# washing-machine.net
KiCad netlist of a schematic drawn in EAGLE
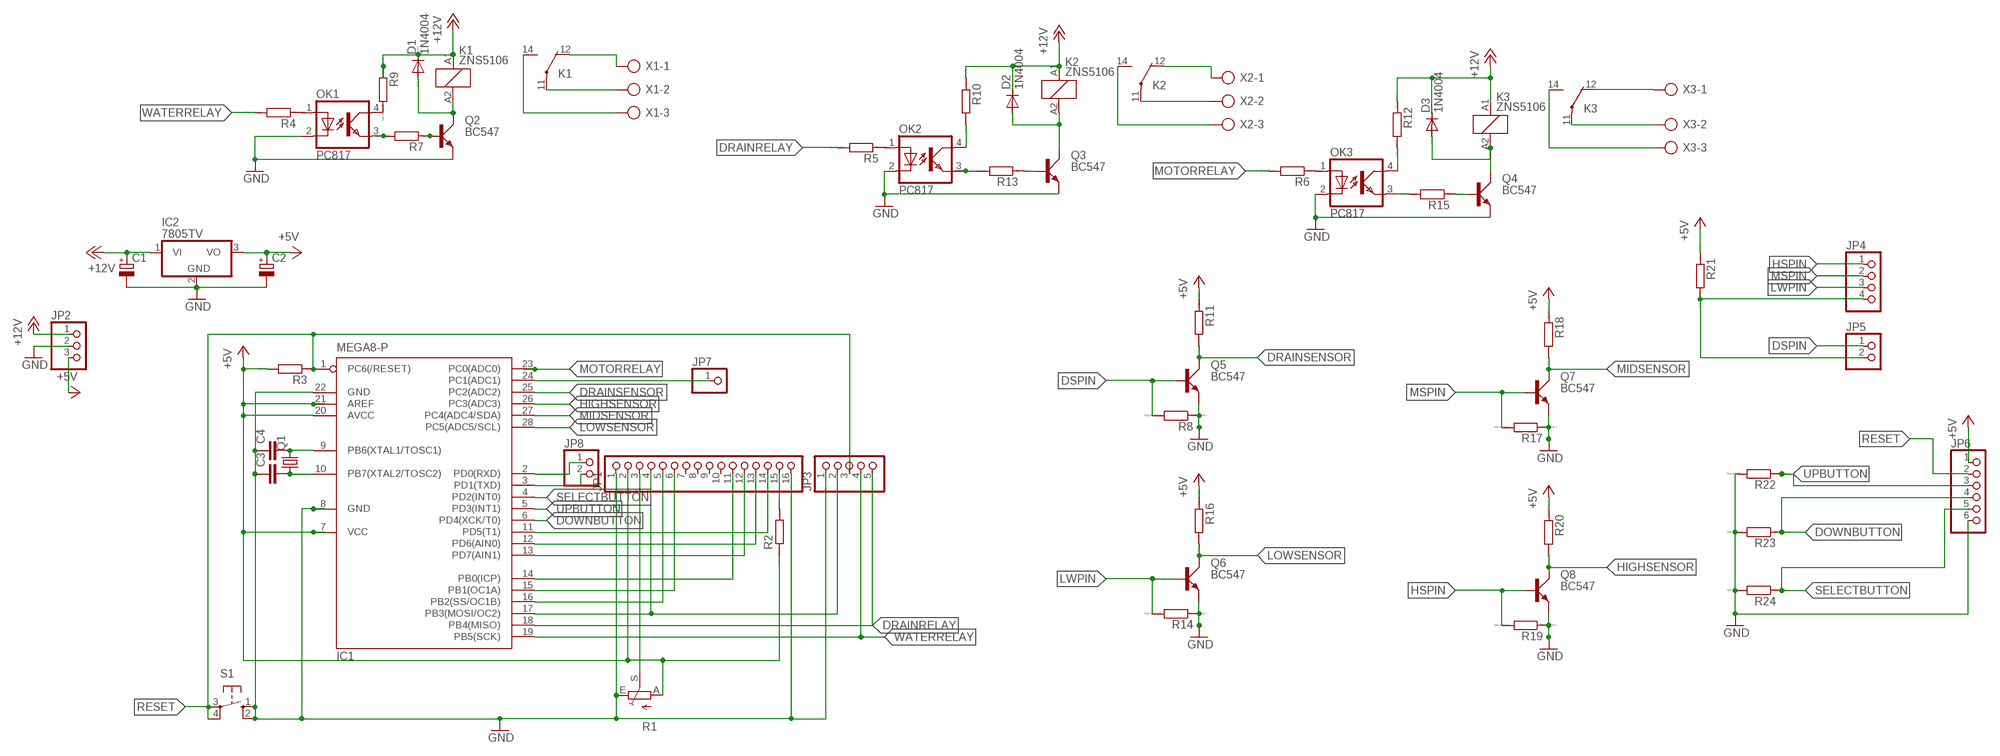
[diagram p0: schematic, sheet 1]

(export (version "E")
  (design (tool "Eeschema 10.0.6"))
  (components
    (comp (ref "C1")
      (value "CPOL-EUE1.8-4")
      (footprint "eagle-import:E1,8-4")
      (libsource (lib "eagle-import") (part "CPOL-EUE1.8-4"))
    )
    (comp (ref "C2")
      (value "CPOL-EUE1.8-4")
      (footprint "eagle-import:E1,8-4")
      (libsource (lib "eagle-import") (part "CPOL-EUE1.8-4"))
    )
    (comp (ref "C3")
      (value "C-EU025-024X044")
      (footprint "eagle-import:C025-024X044")
      (libsource (lib "eagle-import") (part "C-EU025-024X044"))
    )
    (comp (ref "C4")
      (value "C-EU025-024X044")
      (footprint "eagle-import:C025-024X044")
      (libsource (lib "eagle-import") (part "C-EU025-024X044"))
    )
    (comp (ref "D1")
      (value "1N4004")
      (footprint "eagle-import:DO41-10")
      (libsource (lib "eagle-import") (part "1N4004"))
    )
    (comp (ref "D2")
      (value "1N4004")
      (footprint "eagle-import:DO41-10")
      (libsource (lib "eagle-import") (part "1N4004"))
    )
    (comp (ref "D3")
      (value "1N4004")
      (footprint "eagle-import:DO41-10")
      (libsource (lib "eagle-import") (part "1N4004"))
    )
    (comp (ref "IC1")
      (value "MEGA8-P")
      (footprint "eagle-import:DIL28-3")
      (libsource (lib "eagle-import") (part "MEGA8-P"))
    )
    (comp (ref "IC2")
      (value "7805TV")
      (footprint "eagle-import:TO220V")
      (libsource (lib "eagle-import") (part "78TV05"))
    )
    (comp (ref "JP1")
      (value "PINHD-1X16")
      (footprint "eagle-import:1X16")
      (libsource (lib "eagle-import") (part "PINHD-1X16"))
    )
    (comp (ref "JP2")
      (value "PINHD-1X3")
      (footprint "eagle-import:1X03")
      (libsource (lib "eagle-import") (part "PINHD-1X3"))
    )
    (comp (ref "JP3")
      (value "PINHD-1X5")
      (footprint "eagle-import:1X05")
      (libsource (lib "eagle-import") (part "PINHD-1X5"))
    )
    (comp (ref "JP4")
      (value "PINHD-1X4")
      (footprint "eagle-import:1X04")
      (libsource (lib "eagle-import") (part "PINHD-1X4"))
    )
    (comp (ref "JP5")
      (value "PINHD-1X2")
      (footprint "eagle-import:1X02")
      (libsource (lib "eagle-import") (part "PINHD-1X2"))
    )
    (comp (ref "JP6")
      (value "PINHD-1X6")
      (footprint "eagle-import:1X06")
      (libsource (lib "eagle-import") (part "PINHD-1X6"))
    )
    (comp (ref "JP7")
      (value "PINHD-1X1")
      (footprint "eagle-import:1X01")
      (libsource (lib "eagle-import") (part "PINHD-1X1"))
    )
    (comp (ref "JP8")
      (value "PINHD-1X2")
      (footprint "eagle-import:1X02")
      (libsource (lib "eagle-import") (part "PINHD-1X2"))
    )
    (comp (ref "K1")
      (value "ZNS5106")
      (footprint "eagle-import:ZN5")
      (libsource (lib "eagle-import") (part "ZNS5106"))
    )
    (comp (ref "K2")
      (value "ZNS5106")
      (footprint "eagle-import:ZN5")
      (libsource (lib "eagle-import") (part "ZNS5106"))
    )
    (comp (ref "K3")
      (value "ZNS5106")
      (footprint "eagle-import:ZN5")
      (libsource (lib "eagle-import") (part "ZNS5106"))
    )
    (comp (ref "OK1")
      (value "PC817")
      (footprint "eagle-import:DIL04")
      (fields (field (name "MPN") "PC817X4J000F"))
      (libsource (lib "eagle-import") (part "PC817"))
    )
    (comp (ref "OK2")
      (value "PC817")
      (footprint "eagle-import:DIL04")
      (fields (field (name "MPN") "PC817X4J000F"))
      (libsource (lib "eagle-import") (part "PC817"))
    )
    (comp (ref "OK3")
      (value "PC817")
      (footprint "eagle-import:DIL04")
      (fields (field (name "MPN") "PC817X4J000F"))
      (libsource (lib "eagle-import") (part "PC817"))
    )
    (comp (ref "Q1")
      (value "CRYSTALHC49S")
      (footprint "eagle-import:HC49_S")
      (libsource (lib "eagle-import") (part "CRYSTALHC49S"))
    )
    (comp (ref "Q2")
      (value "BC547")
      (footprint "eagle-import:SOT54A")
      (libsource (lib "eagle-import") (part "BC547"))
    )
    (comp (ref "Q3")
      (value "BC547")
      (footprint "eagle-import:SOT54A")
      (libsource (lib "eagle-import") (part "BC547"))
    )
    (comp (ref "Q4")
      (value "BC547")
      (footprint "eagle-import:SOT54A")
      (libsource (lib "eagle-import") (part "BC547"))
    )
    (comp (ref "Q5")
      (value "BC547")
      (footprint "eagle-import:SOT54A")
      (libsource (lib "eagle-import") (part "BC547"))
    )
    (comp (ref "Q6")
      (value "BC547")
      (footprint "eagle-import:SOT54A")
      (libsource (lib "eagle-import") (part "BC547"))
    )
    (comp (ref "Q7")
      (value "BC547")
      (footprint "eagle-import:SOT54A")
      (libsource (lib "eagle-import") (part "BC547"))
    )
    (comp (ref "Q8")
      (value "BC547")
      (footprint "eagle-import:SOT54A")
      (libsource (lib "eagle-import") (part "BC547"))
    )
    (comp (ref "R1")
      (value "TRIM_EU-S63P")
      (footprint "eagle-import:S63P")
      (libsource (lib "eagle-import") (part "TRIM_EU-S63P"))
    )
    (comp (ref "R2")
      (value "R0204/7")
      (footprint "eagle-import:0204_7")
      (libsource (lib "eagle-import") (part "R0204/7"))
    )
    (comp (ref "R3")
      (value "R0204/7")
      (footprint "eagle-import:0204_7")
      (libsource (lib "eagle-import") (part "R0204/7"))
    )
    (comp (ref "R4")
      (value "R0204/7")
      (footprint "eagle-import:0204_7")
      (libsource (lib "eagle-import") (part "R0204/7"))
    )
    (comp (ref "R5")
      (value "R0204/7")
      (footprint "eagle-import:0204_7")
      (libsource (lib "eagle-import") (part "R0204/7"))
    )
    (comp (ref "R6")
      (value "R0204/7")
      (footprint "eagle-import:0204_7")
      (libsource (lib "eagle-import") (part "R0204/7"))
    )
    (comp (ref "R7")
      (value "R0204/7")
      (footprint "eagle-import:0204_7")
      (libsource (lib "eagle-import") (part "R0204/7"))
    )
    (comp (ref "R8")
      (value "R0204/7")
      (footprint "eagle-import:0204_7")
      (libsource (lib "eagle-import") (part "R0204/7"))
    )
    (comp (ref "R9")
      (value "R0204/7")
      (footprint "eagle-import:0204_7")
      (libsource (lib "eagle-import") (part "R0204/7"))
    )
    (comp (ref "R10")
      (value "R0204/7")
      (footprint "eagle-import:0204_7")
      (libsource (lib "eagle-import") (part "R0204/7"))
    )
    (comp (ref "R11")
      (value "R0204/7")
      (footprint "eagle-import:0204_7")
      (libsource (lib "eagle-import") (part "R0204/7"))
    )
    (comp (ref "R12")
      (value "R0204/7")
      (footprint "eagle-import:0204_7")
      (libsource (lib "eagle-import") (part "R0204/7"))
    )
    (comp (ref "R13")
      (value "R0204/7")
      (footprint "eagle-import:0204_7")
      (libsource (lib "eagle-import") (part "R0204/7"))
    )
    (comp (ref "R14")
      (value "R0204/7")
      (footprint "eagle-import:0204_7")
      (libsource (lib "eagle-import") (part "R0204/7"))
    )
    (comp (ref "R15")
      (value "R0204/7")
      (footprint "eagle-import:0204_7")
      (libsource (lib "eagle-import") (part "R0204/7"))
    )
    (comp (ref "R16")
      (value "R0204/7")
      (footprint "eagle-import:0204_7")
      (libsource (lib "eagle-import") (part "R0204/7"))
    )
    (comp (ref "R17")
      (value "R0204/7")
      (footprint "eagle-import:0204_7")
      (libsource (lib "eagle-import") (part "R0204/7"))
    )
    (comp (ref "R18")
      (value "R0204/7")
      (footprint "eagle-import:0204_7")
      (libsource (lib "eagle-import") (part "R0204/7"))
    )
    (comp (ref "R19")
      (value "R0204/7")
      (footprint "eagle-import:0204_7")
      (libsource (lib "eagle-import") (part "R0204/7"))
    )
    (comp (ref "R20")
      (value "R0204/7")
      (footprint "eagle-import:0204_7")
      (libsource (lib "eagle-import") (part "R0204/7"))
    )
    (comp (ref "R21")
      (value "R0204/7")
      (footprint "eagle-import:0204_7")
      (libsource (lib "eagle-import") (part "R0204/7"))
    )
    (comp (ref "R22")
      (value "R0204/7")
      (footprint "eagle-import:0204_7")
      (libsource (lib "eagle-import") (part "R0204/7"))
    )
    (comp (ref "R23")
      (value "R0204/7")
      (footprint "eagle-import:0204_7")
      (libsource (lib "eagle-import") (part "R0204/7"))
    )
    (comp (ref "R24")
      (value "R0204/7")
      (footprint "eagle-import:0204_7")
      (libsource (lib "eagle-import") (part "R0204/7"))
    )
    (comp (ref "S1")
      (value "10-XX")
      (footprint "eagle-import:B3F-10XX")
      (fields (field (name "MPN") "B3F-1000"))
      (libsource (lib "eagle-import") (part "10-XX"))
    )
    (comp (ref "X1")
      (value "AK500/3")
      (footprint "eagle-import:AK500_3")
      (libsource (lib "eagle-import") (part "AK500/3"))
    )
    (comp (ref "X2")
      (value "AK500/3")
      (footprint "eagle-import:AK500_3")
      (libsource (lib "eagle-import") (part "AK500/3"))
    )
    (comp (ref "X3")
      (value "AK500/3")
      (footprint "eagle-import:AK500_3")
      (libsource (lib "eagle-import") (part "AK500/3"))
    )
  )
  (nets
    (net (code "1") (name "+5V") (class "Default")
      (node (ref "C2") (pin "+") (pinfunction "+_+") (pintype "passive"))
      (node (ref "IC1") (pin "20") (pinfunction "AVCC_20") (pintype "power_in"))
      (node (ref "IC1") (pin "21") (pinfunction "AREF_21") (pintype "passive"))
      (node (ref "IC1") (pin "7") (pinfunction "VCC_7") (pintype "power_in"))
      (node (ref "IC2") (pin "3") (pinfunction "VO_3") (pintype "passive"))
      (node (ref "JP1") (pin "2") (pinfunction "2_2") (pintype "passive"))
      (node (ref "JP2") (pin "3") (pinfunction "3_3") (pintype "passive"))
      (node (ref "JP6") (pin "1") (pinfunction "1_1") (pintype "passive"))
      (node (ref "R1") (pin "A") (pinfunction "A_A") (pintype "passive"))
      (node (ref "R11") (pin "1") (pinfunction "1_1") (pintype "passive"))
      (node (ref "R16") (pin "1") (pinfunction "1_1") (pintype "passive"))
      (node (ref "R18") (pin "1") (pinfunction "1_1") (pintype "passive"))
      (node (ref "R2") (pin "1") (pinfunction "1_1") (pintype "passive"))
      (node (ref "R20") (pin "1") (pinfunction "1_1") (pintype "passive"))
      (node (ref "R21") (pin "1") (pinfunction "1_1") (pintype "passive"))
      (node (ref "R3") (pin "2") (pinfunction "2_2") (pintype "passive"))
    )
    (net (code "2") (name "+12V") (class "Default")
      (node (ref "C1") (pin "+") (pinfunction "+_+") (pintype "passive"))
      (node (ref "D1") (pin "C") (pinfunction "C_C") (pintype "passive"))
      (node (ref "D2") (pin "C") (pinfunction "C_C") (pintype "passive"))
      (node (ref "D3") (pin "C") (pinfunction "C_C") (pintype "passive"))
      (node (ref "IC2") (pin "1") (pinfunction "VI_1") (pintype "input"))
      (node (ref "JP2") (pin "1") (pinfunction "1_1") (pintype "passive"))
      (node (ref "K1") (pin "A1") (pinfunction "1_A1") (pintype "passive"))
      (node (ref "K2") (pin "A1") (pinfunction "1_A1") (pintype "passive"))
      (node (ref "K3") (pin "A1") (pinfunction "1_A1") (pintype "passive"))
      (node (ref "R10") (pin "1") (pinfunction "1_1") (pintype "passive"))
      (node (ref "R12") (pin "1") (pinfunction "1_1") (pintype "passive"))
      (node (ref "R9") (pin "1") (pinfunction "1_1") (pintype "passive"))
    )
    (net (code "3") (name "DOWNBUTTON") (class "Default")
      (node (ref "IC1") (pin "6") (pinfunction "PD4(XCK/T0)_6") (pintype "bidirectional"))
      (node (ref "JP6") (pin "4") (pinfunction "4_4") (pintype "passive"))
      (node (ref "R23") (pin "1") (pinfunction "1_1") (pintype "passive"))
    )
    (net (code "4") (name "DRAINRELAY") (class "Default")
      (node (ref "IC1") (pin "18") (pinfunction "PB4(MISO)_18") (pintype "bidirectional"))
      (node (ref "JP3") (pin "5") (pinfunction "5_5") (pintype "passive"))
      (node (ref "R5") (pin "2") (pinfunction "2_2") (pintype "passive"))
    )
    (net (code "5") (name "DRAINSENSOR") (class "Default")
      (node (ref "IC1") (pin "25") (pinfunction "PC2(ADC2)_25") (pintype "bidirectional"))
      (node (ref "Q5") (pin "C") (pinfunction "C_C") (pintype "passive"))
      (node (ref "R11") (pin "2") (pinfunction "2_2") (pintype "passive"))
    )
    (net (code "6") (name "DSPIN") (class "Default")
      (node (ref "JP5") (pin "1") (pinfunction "1_1") (pintype "passive"))
      (node (ref "Q5") (pin "B") (pinfunction "B_B") (pintype "passive"))
      (node (ref "R8") (pin "2") (pinfunction "2_2") (pintype "passive"))
    )
    (net (code "7") (name "GND") (class "Default")
      (node (ref "C1") (pin "-") (pinfunction "-_-") (pintype "passive"))
      (node (ref "C2") (pin "-") (pinfunction "-_-") (pintype "passive"))
      (node (ref "C3") (pin "1") (pinfunction "1_1") (pintype "passive"))
      (node (ref "C4") (pin "1") (pinfunction "1_1") (pintype "passive"))
      (node (ref "IC1") (pin "22") (pinfunction "GND_22") (pintype "power_in"))
      (node (ref "IC1") (pin "8") (pinfunction "GND_8") (pintype "power_in"))
      (node (ref "IC2") (pin "2") (pinfunction "GND_2") (pintype "passive"))
      (node (ref "JP1") (pin "1") (pinfunction "1_1") (pintype "passive"))
      (node (ref "JP1") (pin "16") (pinfunction "16_16") (pintype "passive"))
      (node (ref "JP2") (pin "2") (pinfunction "2_2") (pintype "passive"))
      (node (ref "JP3") (pin "1") (pinfunction "1_1") (pintype "passive"))
      (node (ref "JP6") (pin "6") (pinfunction "6_6") (pintype "passive"))
      (node (ref "OK1") (pin "2") (pinfunction "C_2") (pintype "passive"))
      (node (ref "OK2") (pin "2") (pinfunction "C_2") (pintype "passive"))
      (node (ref "OK3") (pin "2") (pinfunction "C_2") (pintype "passive"))
      (node (ref "Q2") (pin "E") (pinfunction "E_E") (pintype "passive"))
      (node (ref "Q3") (pin "E") (pinfunction "E_E") (pintype "passive"))
      (node (ref "Q4") (pin "E") (pinfunction "E_E") (pintype "passive"))
      (node (ref "Q5") (pin "E") (pinfunction "E_E") (pintype "passive"))
      (node (ref "Q6") (pin "E") (pinfunction "E_E") (pintype "passive"))
      (node (ref "Q7") (pin "E") (pinfunction "E_E") (pintype "passive"))
      (node (ref "Q8") (pin "E") (pinfunction "E_E") (pintype "passive"))
      (node (ref "R1") (pin "E") (pinfunction "E_E") (pintype "passive"))
      (node (ref "R14") (pin "1") (pinfunction "1_1") (pintype "passive"))
      (node (ref "R17") (pin "1") (pinfunction "1_1") (pintype "passive"))
      (node (ref "R19") (pin "1") (pinfunction "1_1") (pintype "passive"))
      (node (ref "R22") (pin "2") (pinfunction "2_2") (pintype "passive"))
      (node (ref "R23") (pin "2") (pinfunction "2_2") (pintype "passive"))
      (node (ref "R24") (pin "2") (pinfunction "2_2") (pintype "passive"))
      (node (ref "R8") (pin "1") (pinfunction "1_1") (pintype "passive"))
      (node (ref "S1") (pin "1") (pinfunction "S_1") (pintype "passive"))
      (node (ref "S1") (pin "2") (pinfunction "S1_2") (pintype "passive"))
    )
    (net (code "8") (name "HIGHSENSOR") (class "Default")
      (node (ref "IC1") (pin "26") (pinfunction "PC3(ADC3)_26") (pintype "bidirectional"))
      (node (ref "Q8") (pin "C") (pinfunction "C_C") (pintype "passive"))
      (node (ref "R20") (pin "2") (pinfunction "2_2") (pintype "passive"))
    )
    (net (code "9") (name "HSPIN") (class "Default")
      (node (ref "JP4") (pin "1") (pinfunction "1_1") (pintype "passive"))
      (node (ref "Q8") (pin "B") (pinfunction "B_B") (pintype "passive"))
      (node (ref "R19") (pin "2") (pinfunction "2_2") (pintype "passive"))
    )
    (net (code "10") (name "LOWSENSOR") (class "Default")
      (node (ref "IC1") (pin "28") (pinfunction "PC5(ADC5/SCL)_28") (pintype "bidirectional"))
      (node (ref "Q6") (pin "C") (pinfunction "C_C") (pintype "passive"))
      (node (ref "R16") (pin "2") (pinfunction "2_2") (pintype "passive"))
    )
    (net (code "11") (name "LWPIN") (class "Default")
      (node (ref "JP4") (pin "3") (pinfunction "3_3") (pintype "passive"))
      (node (ref "Q6") (pin "B") (pinfunction "B_B") (pintype "passive"))
      (node (ref "R14") (pin "2") (pinfunction "2_2") (pintype "passive"))
    )
    (net (code "12") (name "MIDSENSOR") (class "Default")
      (node (ref "IC1") (pin "27") (pinfunction "PC4(ADC4/SDA)_27") (pintype "bidirectional"))
      (node (ref "Q7") (pin "C") (pinfunction "C_C") (pintype "passive"))
      (node (ref "R18") (pin "2") (pinfunction "2_2") (pintype "passive"))
    )
    (net (code "13") (name "MOTORRELAY") (class "Default")
      (node (ref "IC1") (pin "23") (pinfunction "PC0(ADC0)_23") (pintype "bidirectional"))
      (node (ref "R6") (pin "2") (pinfunction "2_2") (pintype "passive"))
    )
    (net (code "14") (name "MSPIN") (class "Default")
      (node (ref "JP4") (pin "2") (pinfunction "2_2") (pintype "passive"))
      (node (ref "Q7") (pin "B") (pinfunction "B_B") (pintype "passive"))
      (node (ref "R17") (pin "2") (pinfunction "2_2") (pintype "passive"))
    )
    (net (code "15") (name "Net-(IC1-PB0(ICP))") (class "Default")
      (node (ref "IC1") (pin "14") (pinfunction "PB0(ICP)_14") (pintype "bidirectional"))
      (node (ref "JP1") (pin "11") (pinfunction "11_11") (pintype "passive"))
    )
    (net (code "16") (name "Net-(IC1-PB1(OC1A))") (class "Default")
      (node (ref "IC1") (pin "15") (pinfunction "PB1(OC1A)_15") (pintype "bidirectional"))
      (node (ref "JP1") (pin "6") (pinfunction "6_6") (pintype "passive"))
    )
    (net (code "17") (name "Net-(IC1-PB2(SS{slash}OC1B))") (class "Default")
      (node (ref "IC1") (pin "16") (pinfunction "PB2(SS/OC1B)_16") (pintype "bidirectional"))
      (node (ref "JP1") (pin "5") (pinfunction "5_5") (pintype "passive"))
    )
    (net (code "18") (name "Net-(IC1-PB3(MOSI{slash}OC2))") (class "Default")
      (node (ref "IC1") (pin "17") (pinfunction "PB3(MOSI/OC2)_17") (pintype "bidirectional"))
      (node (ref "JP1") (pin "4") (pinfunction "4_4") (pintype "passive"))
      (node (ref "JP3") (pin "2") (pinfunction "2_2") (pintype "passive"))
    )
    (net (code "19") (name "Net-(IC1-PB6(XTAL1{slash}TOSC1))") (class "Default")
      (node (ref "C4") (pin "2") (pinfunction "2_2") (pintype "passive"))
      (node (ref "IC1") (pin "9") (pinfunction "PB6(XTAL1/TOSC1)_9") (pintype "bidirectional"))
      (node (ref "Q1") (pin "2") (pinfunction "2_2") (pintype "passive"))
    )
    (net (code "20") (name "Net-(IC1-PB7(XTAL2{slash}TOSC2))") (class "Default")
      (node (ref "C3") (pin "2") (pinfunction "2_2") (pintype "passive"))
      (node (ref "IC1") (pin "10") (pinfunction "PB7(XTAL2/TOSC2)_10") (pintype "bidirectional"))
      (node (ref "Q1") (pin "1") (pinfunction "1_1") (pintype "passive"))
    )
    (net (code "21") (name "Net-(IC1-PC1(ADC1))") (class "Default")
      (node (ref "IC1") (pin "24") (pinfunction "PC1(ADC1)_24") (pintype "bidirectional"))
      (node (ref "JP7") (pin "1") (pinfunction "1_1") (pintype "passive"))
    )
    (net (code "22") (name "Net-(IC1-PD0(RXD))") (class "Default")
      (node (ref "IC1") (pin "2") (pinfunction "PD0(RXD)_2") (pintype "bidirectional"))
      (node (ref "JP8") (pin "1") (pinfunction "1_1") (pintype "passive"))
    )
    (net (code "23") (name "Net-(IC1-PD1(TXD))") (class "Default")
      (node (ref "IC1") (pin "3") (pinfunction "PD1(TXD)_3") (pintype "bidirectional"))
      (node (ref "JP8") (pin "2") (pinfunction "2_2") (pintype "passive"))
    )
    (net (code "24") (name "Net-(IC1-PD5(T1))") (class "Default")
      (node (ref "IC1") (pin "11") (pinfunction "PD5(T1)_11") (pintype "bidirectional"))
      (node (ref "JP1") (pin "14") (pinfunction "14_14") (pintype "passive"))
    )
    (net (code "25") (name "Net-(IC1-PD6(AIN0))") (class "Default")
      (node (ref "IC1") (pin "12") (pinfunction "PD6(AIN0)_12") (pintype "bidirectional"))
      (node (ref "JP1") (pin "13") (pinfunction "13_13") (pintype "passive"))
    )
    (net (code "26") (name "Net-(IC1-PD7(AIN1))") (class "Default")
      (node (ref "IC1") (pin "13") (pinfunction "PD7(AIN1)_13") (pintype "bidirectional"))
      (node (ref "JP1") (pin "12") (pinfunction "12_12") (pintype "passive"))
    )
    (net (code "27") (name "Net-(JP1-Pad3)") (class "Default")
      (node (ref "JP1") (pin "3") (pinfunction "3_3") (pintype "passive"))
      (node (ref "R1") (pin "S") (pinfunction "S_S") (pintype "passive"))
    )
    (net (code "28") (name "Net-(JP1-Pad15)") (class "Default")
      (node (ref "JP1") (pin "15") (pinfunction "15_15") (pintype "passive"))
      (node (ref "R2") (pin "2") (pinfunction "2_2") (pintype "passive"))
    )
    (net (code "29") (name "Net-(JP4-Pad4)") (class "Default")
      (node (ref "JP4") (pin "4") (pinfunction "4_4") (pintype "passive"))
      (node (ref "JP5") (pin "2") (pinfunction "2_2") (pintype "passive"))
      (node (ref "R21") (pin "2") (pinfunction "2_2") (pintype "passive"))
    )
    (net (code "30") (name "Net-(K1A-2)") (class "Default")
      (node (ref "D1") (pin "A") (pinfunction "A_A") (pintype "passive"))
      (node (ref "K1") (pin "A2") (pinfunction "2_A2") (pintype "passive"))
      (node (ref "Q2") (pin "C") (pinfunction "C_C") (pintype "passive"))
    )
    (net (code "31") (name "Net-(K1B-O)") (class "Default")
      (node (ref "K1") (pin "12") (pinfunction "O_12") (pintype "passive"))
      (node (ref "X1") (pin "1") (pinfunction "KL_1") (pintype "passive"))
    )
    (net (code "32") (name "Net-(K1B-P)") (class "Default")
      (node (ref "K1") (pin "11") (pinfunction "P_11") (pintype "passive"))
      (node (ref "X1") (pin "2") (pinfunction "KL_2") (pintype "passive"))
    )
    (net (code "33") (name "Net-(K1B-S)") (class "Default")
      (node (ref "K1") (pin "14") (pinfunction "S_14") (pintype "passive"))
      (node (ref "X1") (pin "3") (pinfunction "KL_3") (pintype "passive"))
    )
    (net (code "34") (name "Net-(K2A-2)") (class "Default")
      (node (ref "D2") (pin "A") (pinfunction "A_A") (pintype "passive"))
      (node (ref "K2") (pin "A2") (pinfunction "2_A2") (pintype "passive"))
      (node (ref "Q3") (pin "C") (pinfunction "C_C") (pintype "passive"))
    )
    (net (code "35") (name "Net-(K2B-O)") (class "Default")
      (node (ref "K2") (pin "12") (pinfunction "O_12") (pintype "passive"))
      (node (ref "X2") (pin "1") (pinfunction "KL_1") (pintype "passive"))
    )
    (net (code "36") (name "Net-(K2B-P)") (class "Default")
      (node (ref "K2") (pin "11") (pinfunction "P_11") (pintype "passive"))
      (node (ref "X2") (pin "2") (pinfunction "KL_2") (pintype "passive"))
    )
    (net (code "37") (name "Net-(K2B-S)") (class "Default")
      (node (ref "K2") (pin "14") (pinfunction "S_14") (pintype "passive"))
      (node (ref "X2") (pin "3") (pinfunction "KL_3") (pintype "passive"))
    )
    (net (code "38") (name "Net-(K3A-2)") (class "Default")
      (node (ref "D3") (pin "A") (pinfunction "A_A") (pintype "passive"))
      (node (ref "K3") (pin "A2") (pinfunction "2_A2") (pintype "passive"))
      (node (ref "Q4") (pin "C") (pinfunction "C_C") (pintype "passive"))
    )
    (net (code "39") (name "Net-(K3B-O)") (class "Default")
      (node (ref "K3") (pin "12") (pinfunction "O_12") (pintype "passive"))
      (node (ref "X3") (pin "1") (pinfunction "KL_1") (pintype "passive"))
    )
    (net (code "40") (name "Net-(K3B-P)") (class "Default")
      (node (ref "K3") (pin "11") (pinfunction "P_11") (pintype "passive"))
      (node (ref "X3") (pin "2") (pinfunction "KL_2") (pintype "passive"))
    )
    (net (code "41") (name "Net-(K3B-S)") (class "Default")
      (node (ref "K3") (pin "14") (pinfunction "S_14") (pintype "passive"))
      (node (ref "X3") (pin "3") (pinfunction "KL_3") (pintype "passive"))
    )
    (net (code "42") (name "Net-(OK1-A)") (class "Default")
      (node (ref "OK1") (pin "1") (pinfunction "A_1") (pintype "passive"))
      (node (ref "R4") (pin "1") (pinfunction "1_1") (pintype "passive"))
    )
    (net (code "43") (name "Net-(OK1-COL)") (class "Default")
      (node (ref "OK1") (pin "4") (pinfunction "COL_4") (pintype "passive"))
      (node (ref "R9") (pin "2") (pinfunction "2_2") (pintype "passive"))
    )
    (net (code "44") (name "Net-(OK1-EMIT)") (class "Default")
      (node (ref "OK1") (pin "3") (pinfunction "EMIT_3") (pintype "passive"))
      (node (ref "R7") (pin "2") (pinfunction "2_2") (pintype "passive"))
    )
    (net (code "45") (name "Net-(OK2-A)") (class "Default")
      (node (ref "OK2") (pin "1") (pinfunction "A_1") (pintype "passive"))
      (node (ref "R5") (pin "1") (pinfunction "1_1") (pintype "passive"))
    )
    (net (code "46") (name "Net-(OK2-COL)") (class "Default")
      (node (ref "OK2") (pin "4") (pinfunction "COL_4") (pintype "passive"))
      (node (ref "R10") (pin "2") (pinfunction "2_2") (pintype "passive"))
    )
    (net (code "47") (name "Net-(OK2-EMIT)") (class "Default")
      (node (ref "OK2") (pin "3") (pinfunction "EMIT_3") (pintype "passive"))
      (node (ref "R13") (pin "2") (pinfunction "2_2") (pintype "passive"))
    )
    (net (code "48") (name "Net-(OK3-A)") (class "Default")
      (node (ref "OK3") (pin "1") (pinfunction "A_1") (pintype "passive"))
      (node (ref "R6") (pin "1") (pinfunction "1_1") (pintype "passive"))
    )
    (net (code "49") (name "Net-(OK3-COL)") (class "Default")
      (node (ref "OK3") (pin "4") (pinfunction "COL_4") (pintype "passive"))
      (node (ref "R12") (pin "2") (pinfunction "2_2") (pintype "passive"))
    )
    (net (code "50") (name "Net-(OK3-EMIT)") (class "Default")
      (node (ref "OK3") (pin "3") (pinfunction "EMIT_3") (pintype "passive"))
      (node (ref "R15") (pin "2") (pinfunction "2_2") (pintype "passive"))
    )
    (net (code "51") (name "Net-(Q2-PadB)") (class "Default")
      (node (ref "Q2") (pin "B") (pinfunction "B_B") (pintype "passive"))
      (node (ref "R7") (pin "1") (pinfunction "1_1") (pintype "passive"))
    )
    (net (code "52") (name "Net-(Q3-PadB)") (class "Default")
      (node (ref "Q3") (pin "B") (pinfunction "B_B") (pintype "passive"))
      (node (ref "R13") (pin "1") (pinfunction "1_1") (pintype "passive"))
    )
    (net (code "53") (name "Net-(Q4-PadB)") (class "Default")
      (node (ref "Q4") (pin "B") (pinfunction "B_B") (pintype "passive"))
      (node (ref "R15") (pin "1") (pinfunction "1_1") (pintype "passive"))
    )
    (net (code "54") (name "RESET") (class "Default")
      (node (ref "IC1") (pin "1") (pinfunction "PC6(/RESET)_1") (pintype "bidirectional"))
      (node (ref "JP3") (pin "3") (pinfunction "3_3") (pintype "passive"))
      (node (ref "JP6") (pin "2") (pinfunction "2_2") (pintype "passive"))
      (node (ref "R3") (pin "1") (pinfunction "1_1") (pintype "passive"))
      (node (ref "S1") (pin "3") (pinfunction "P_3") (pintype "passive"))
      (node (ref "S1") (pin "4") (pinfunction "P1_4") (pintype "passive"))
    )
    (net (code "55") (name "SELECTBUTTON") (class "Default")
      (node (ref "IC1") (pin "4") (pinfunction "PD2(INT0)_4") (pintype "bidirectional"))
      (node (ref "JP6") (pin "5") (pinfunction "5_5") (pintype "passive"))
      (node (ref "R24") (pin "1") (pinfunction "1_1") (pintype "passive"))
    )
    (net (code "56") (name "UPBUTTON") (class "Default")
      (node (ref "IC1") (pin "5") (pinfunction "PD3(INT1)_5") (pintype "bidirectional"))
      (node (ref "JP6") (pin "3") (pinfunction "3_3") (pintype "passive"))
      (node (ref "R22") (pin "1") (pinfunction "1_1") (pintype "passive"))
    )
    (net (code "57") (name "WATERRELAY") (class "Default")
      (node (ref "IC1") (pin "19") (pinfunction "PB5(SCK)_19") (pintype "bidirectional"))
      (node (ref "JP3") (pin "4") (pinfunction "4_4") (pintype "passive"))
      (node (ref "R4") (pin "2") (pinfunction "2_2") (pintype "passive"))
    )
    (net (code "58") (name "unconnected-(JP1-Pad7)") (class "Default")
      (node (ref "JP1") (pin "7") (pinfunction "7_7") (pintype "passive"))
    )
    (net (code "59") (name "unconnected-(JP1-Pad8)") (class "Default")
      (node (ref "JP1") (pin "8") (pinfunction "8_8") (pintype "passive"))
    )
    (net (code "60") (name "unconnected-(JP1-Pad9)") (class "Default")
      (node (ref "JP1") (pin "9") (pinfunction "9_9") (pintype "passive"))
    )
    (net (code "61") (name "unconnected-(JP1-Pad10)") (class "Default")
      (node (ref "JP1") (pin "10") (pinfunction "10_10") (pintype "passive"))
    )
  )
)
